# I2C_MUX.net
KiCad netlist of a schematic drawn in Altium Designer
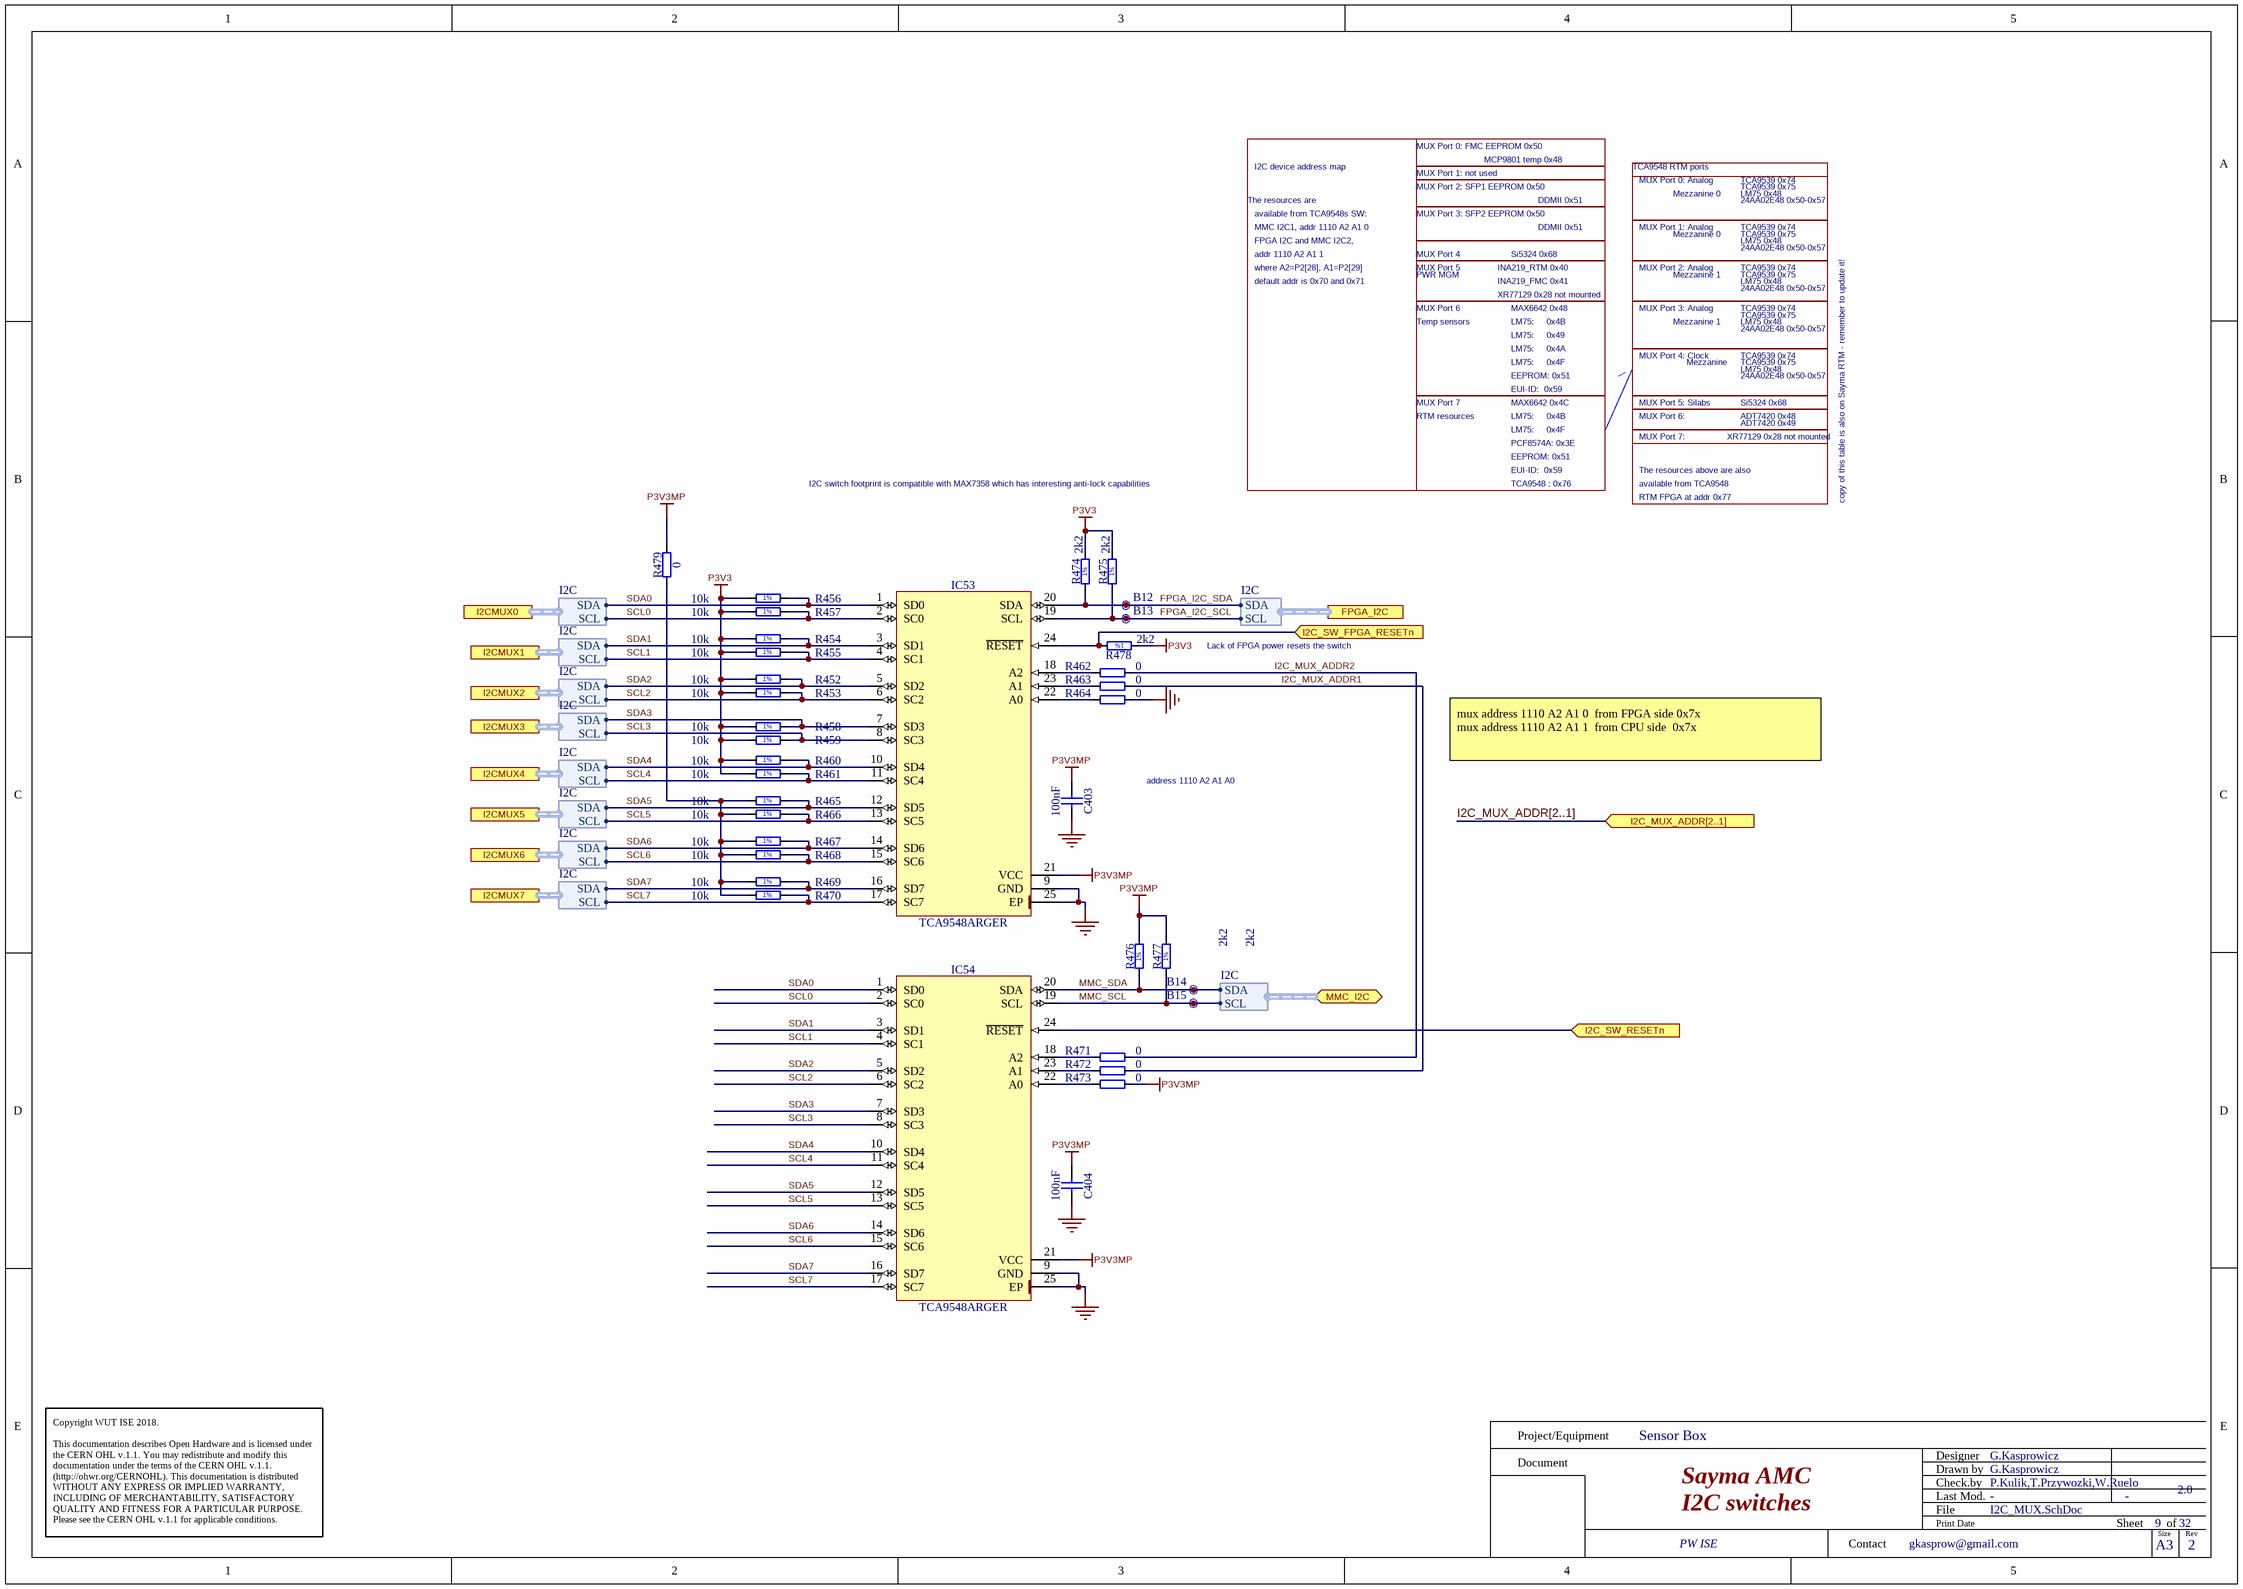
[diagram p0: I2C_MUX.SchDoc]

(export (version "E")
  (design (tool "Eeschema 10.0.6"))
  (components
    (comp (ref "B12")
      (value "SMD_PAD_D1MM")
      (footprint "C100")
      (libsource (lib "altium-import") (part "root_0__*"))
    )
    (comp (ref "B13")
      (value "SMD_PAD_D1MM")
      (footprint "C100")
      (libsource (lib "altium-import") (part "root_0__*"))
    )
    (comp (ref "B14")
      (value "SMD_PAD_D1MM")
      (footprint "C100")
      (libsource (lib "altium-import") (part "root_0__*"))
    )
    (comp (ref "B15")
      (value "SMD_PAD_D1MM")
      (footprint "C100")
      (libsource (lib "altium-import") (part "root_0__*"))
    )
    (comp (ref "C403")
      (value "100nF")
      (footprint "CAPC0603X33N")
      (description "Non-polarised capacitor")
      (fields
        (field (name "MANUFACTURER PART NUMBER") "CC0201_100NF_6.3V_10%_X5R")
        (field (name "MANUFACTURER") "GENERIC")
        (field (name "AUTHOR") "CERN DEM JLC")
      )
      (libsource (lib "Capacitors") (part "Capacitor - non polarized"))
    )
    (comp (ref "C404")
      (value "100nF")
      (footprint "CAPC0603X33N")
      (description "Non-polarised capacitor")
      (fields
        (field (name "MANUFACTURER PART NUMBER") "CC0201_100NF_6.3V_10%_X5R")
        (field (name "MANUFACTURER") "GENERIC")
        (field (name "AUTHOR") "CERN DEM JLC")
      )
      (libsource (lib "Capacitors") (part "Capacitor - non polarized"))
    )
    (comp (ref "IC53")
      (value "TCA9548ARGER")
      (footprint "QFN50P400X400X100-25N-S220")
      (description "Low Voltage 8-Channel I2C Switch With Reset")
      (fields (field (name "MANUFACTURER") "TEXAS INSTRUMENTS") (field (name "AUTHOR") "CERN DEM JLC"))
      (libsource (lib "ICs And Semiconductors") (part "TCA9548ARGER"))
    )
    (comp (ref "IC54")
      (value "TCA9548ARGER")
      (footprint "QFN50P400X400X100-25N-S220")
      (description "Low Voltage 8-Channel I2C Switch With Reset")
      (fields (field (name "MANUFACTURER") "TEXAS INSTRUMENTS") (field (name "AUTHOR") "CERN DEM JLC"))
      (libsource (lib "ICs And Semiconductors") (part "TCA9548ARGER"))
    )
    (comp (ref "R452")
      (value "10k")
      (footprint "RESC1005X40N")
      (description "Resistor - 1%")
      (fields
        (field (name "MANUFACTURER PART NUMBER") "R0402_10K_1%_0.0625W_100PPM")
        (field (name "MANUFACTURER") "GENERIC")
        (field (name "AUTHOR") "CERN DEM JLC")
      )
      (libsource (lib "Resistors") (part "Resistor - 1%"))
    )
    (comp (ref "R453")
      (value "10k")
      (footprint "RESC1005X40N")
      (description "Resistor - 1%")
      (fields
        (field (name "MANUFACTURER PART NUMBER") "R0402_10K_1%_0.0625W_100PPM")
        (field (name "MANUFACTURER") "GENERIC")
        (field (name "AUTHOR") "CERN DEM JLC")
      )
      (libsource (lib "Resistors") (part "Resistor - 1%"))
    )
    (comp (ref "R454")
      (value "10k")
      (footprint "RESC1005X40N")
      (description "Resistor - 1%")
      (fields
        (field (name "MANUFACTURER PART NUMBER") "R0402_10K_1%_0.0625W_100PPM")
        (field (name "MANUFACTURER") "GENERIC")
        (field (name "AUTHOR") "CERN DEM JLC")
      )
      (libsource (lib "Resistors") (part "Resistor - 1%"))
    )
    (comp (ref "R455")
      (value "10k")
      (footprint "RESC1005X40N")
      (description "Resistor - 1%")
      (fields
        (field (name "MANUFACTURER PART NUMBER") "R0402_10K_1%_0.0625W_100PPM")
        (field (name "MANUFACTURER") "GENERIC")
        (field (name "AUTHOR") "CERN DEM JLC")
      )
      (libsource (lib "Resistors") (part "Resistor - 1%"))
    )
    (comp (ref "R456")
      (value "10k")
      (footprint "RESC1005X40N")
      (description "Resistor - 1%")
      (fields
        (field (name "MANUFACTURER PART NUMBER") "R0402_10K_1%_0.0625W_100PPM")
        (field (name "MANUFACTURER") "GENERIC")
        (field (name "AUTHOR") "CERN DEM JLC")
      )
      (libsource (lib "Resistors") (part "Resistor - 1%"))
    )
    (comp (ref "R457")
      (value "10k")
      (footprint "RESC1005X40N")
      (description "Resistor - 1%")
      (fields
        (field (name "MANUFACTURER PART NUMBER") "R0402_10K_1%_0.0625W_100PPM")
        (field (name "MANUFACTURER") "GENERIC")
        (field (name "AUTHOR") "CERN DEM JLC")
      )
      (libsource (lib "Resistors") (part "Resistor - 1%"))
    )
    (comp (ref "R458")
      (value "10k")
      (footprint "RESC1005X40N")
      (description "Resistor - 1%")
      (fields
        (field (name "MANUFACTURER PART NUMBER") "R0402_10K_1%_0.0625W_100PPM")
        (field (name "MANUFACTURER") "GENERIC")
        (field (name "AUTHOR") "CERN DEM JLC")
      )
      (libsource (lib "Resistors") (part "Resistor - 1%"))
    )
    (comp (ref "R459")
      (value "10k")
      (footprint "RESC1005X40N")
      (description "Resistor - 1%")
      (fields
        (field (name "MANUFACTURER PART NUMBER") "R0402_10K_1%_0.0625W_100PPM")
        (field (name "MANUFACTURER") "GENERIC")
        (field (name "AUTHOR") "CERN DEM JLC")
      )
      (libsource (lib "Resistors") (part "Resistor - 1%"))
    )
    (comp (ref "R460")
      (value "10k")
      (footprint "RESC1005X40N")
      (description "Resistor - 1%")
      (fields
        (field (name "MANUFACTURER PART NUMBER") "R0402_10K_1%_0.0625W_100PPM")
        (field (name "MANUFACTURER") "GENERIC")
        (field (name "AUTHOR") "CERN DEM JLC")
      )
      (libsource (lib "Resistors") (part "Resistor - 1%"))
    )
    (comp (ref "R461")
      (value "10k")
      (footprint "RESC1005X40N")
      (description "Resistor - 1%")
      (fields
        (field (name "MANUFACTURER PART NUMBER") "R0402_10K_1%_0.0625W_100PPM")
        (field (name "MANUFACTURER") "GENERIC")
        (field (name "AUTHOR") "CERN DEM JLC")
      )
      (libsource (lib "Resistors") (part "Resistor - 1%"))
    )
    (comp (ref "R462")
      (value "0")
      (footprint "RESC1005X40N")
      (description "Resistor")
      (fields
        (field (name "MANUFACTURER PART NUMBER") "R0402_0R_JUMPER")
        (field (name "MANUFACTURER") "GENERIC")
        (field (name "AUTHOR") "CERN DEM JLC")
      )
      (libsource (lib "Resistors") (part "Resistor"))
    )
    (comp (ref "R463")
      (value "0")
      (footprint "RESC1005X40N")
      (description "Resistor")
      (fields
        (field (name "MANUFACTURER PART NUMBER") "R0402_0R_JUMPER")
        (field (name "MANUFACTURER") "GENERIC")
        (field (name "AUTHOR") "CERN DEM JLC")
      )
      (libsource (lib "Resistors") (part "Resistor"))
    )
    (comp (ref "R464")
      (value "0")
      (footprint "RESC1005X40N")
      (description "Resistor")
      (fields
        (field (name "MANUFACTURER PART NUMBER") "R0402_0R_JUMPER")
        (field (name "MANUFACTURER") "GENERIC")
        (field (name "AUTHOR") "CERN DEM JLC")
      )
      (libsource (lib "Resistors") (part "Resistor"))
    )
    (comp (ref "R465")
      (value "10k")
      (footprint "RESC1005X40N")
      (description "Resistor - 1%")
      (fields
        (field (name "MANUFACTURER PART NUMBER") "R0402_10K_1%_0.0625W_100PPM")
        (field (name "MANUFACTURER") "GENERIC")
        (field (name "AUTHOR") "CERN DEM JLC")
      )
      (libsource (lib "Resistors") (part "Resistor - 1%"))
    )
    (comp (ref "R466")
      (value "10k")
      (footprint "RESC1005X40N")
      (description "Resistor - 1%")
      (fields
        (field (name "MANUFACTURER PART NUMBER") "R0402_10K_1%_0.0625W_100PPM")
        (field (name "MANUFACTURER") "GENERIC")
        (field (name "AUTHOR") "CERN DEM JLC")
      )
      (libsource (lib "Resistors") (part "Resistor - 1%"))
    )
    (comp (ref "R467")
      (value "10k")
      (footprint "RESC1005X40N")
      (description "Resistor - 1%")
      (fields
        (field (name "MANUFACTURER PART NUMBER") "R0402_10K_1%_0.0625W_100PPM")
        (field (name "MANUFACTURER") "GENERIC")
        (field (name "AUTHOR") "CERN DEM JLC")
      )
      (libsource (lib "Resistors") (part "Resistor - 1%"))
    )
    (comp (ref "R468")
      (value "10k")
      (footprint "RESC1005X40N")
      (description "Resistor - 1%")
      (fields
        (field (name "MANUFACTURER PART NUMBER") "R0402_10K_1%_0.0625W_100PPM")
        (field (name "MANUFACTURER") "GENERIC")
        (field (name "AUTHOR") "CERN DEM JLC")
      )
      (libsource (lib "Resistors") (part "Resistor - 1%"))
    )
    (comp (ref "R469")
      (value "10k")
      (footprint "RESC1005X40N")
      (description "Resistor - 1%")
      (fields
        (field (name "MANUFACTURER PART NUMBER") "R0402_10K_1%_0.0625W_100PPM")
        (field (name "MANUFACTURER") "GENERIC")
        (field (name "AUTHOR") "CERN DEM JLC")
      )
      (libsource (lib "Resistors") (part "Resistor - 1%"))
    )
    (comp (ref "R470")
      (value "10k")
      (footprint "RESC1005X40N")
      (description "Resistor - 1%")
      (fields
        (field (name "MANUFACTURER PART NUMBER") "R0402_10K_1%_0.0625W_100PPM")
        (field (name "MANUFACTURER") "GENERIC")
        (field (name "AUTHOR") "CERN DEM JLC")
      )
      (libsource (lib "Resistors") (part "Resistor - 1%"))
    )
    (comp (ref "R471")
      (value "0")
      (footprint "RESC1005X40N")
      (description "Resistor")
      (fields
        (field (name "MANUFACTURER PART NUMBER") "R0402_0R_JUMPER")
        (field (name "MANUFACTURER") "GENERIC")
        (field (name "AUTHOR") "CERN DEM JLC")
      )
      (libsource (lib "Resistors") (part "Resistor"))
    )
    (comp (ref "R472")
      (value "0")
      (footprint "RESC1005X40N")
      (description "Resistor")
      (fields
        (field (name "MANUFACTURER PART NUMBER") "R0402_0R_JUMPER")
        (field (name "MANUFACTURER") "GENERIC")
        (field (name "AUTHOR") "CERN DEM JLC")
      )
      (libsource (lib "Resistors") (part "Resistor"))
    )
    (comp (ref "R473")
      (value "0")
      (footprint "RESC1005X40N")
      (description "Resistor")
      (fields
        (field (name "MANUFACTURER PART NUMBER") "R0402_0R_JUMPER")
        (field (name "MANUFACTURER") "GENERIC")
        (field (name "AUTHOR") "CERN DEM JLC")
      )
      (libsource (lib "Resistors") (part "Resistor"))
    )
    (comp (ref "R474")
      (value "2k2")
      (footprint "RESC1005X40N")
      (description "Resistor - 1%")
      (fields
        (field (name "MANUFACTURER PART NUMBER") "R0402_2K2_1%_0.0625W_100PPM")
        (field (name "MANUFACTURER") "GENERIC")
        (field (name "AUTHOR") "CERN DEM JLC")
      )
      (libsource (lib "Resistors") (part "Resistor - 1%"))
    )
    (comp (ref "R475")
      (value "2k2")
      (footprint "RESC1005X40N")
      (description "Resistor - 1%")
      (fields
        (field (name "MANUFACTURER PART NUMBER") "R0402_2K2_1%_0.0625W_100PPM")
        (field (name "MANUFACTURER") "GENERIC")
        (field (name "AUTHOR") "CERN DEM JLC")
      )
      (libsource (lib "Resistors") (part "Resistor - 1%"))
    )
    (comp (ref "R476")
      (value "2k2")
      (footprint "RESC1005X40N")
      (description "Resistor - 1%")
      (fields
        (field (name "MANUFACTURER PART NUMBER") "R0402_2K2_1%_0.0625W_100PPM")
        (field (name "MANUFACTURER") "GENERIC")
        (field (name "AUTHOR") "CERN DEM JLC")
      )
      (libsource (lib "Resistors") (part "Resistor - 1%"))
    )
    (comp (ref "R477")
      (value "2k2")
      (footprint "RESC1005X40N")
      (description "Resistor - 1%")
      (fields
        (field (name "MANUFACTURER PART NUMBER") "R0402_2K2_1%_0.0625W_100PPM")
        (field (name "MANUFACTURER") "GENERIC")
        (field (name "AUTHOR") "CERN DEM JLC")
      )
      (libsource (lib "Resistors") (part "Resistor - 1%"))
    )
    (comp (ref "R478")
      (value "2k2")
      (footprint "RESC1005X40N")
      (description "Resistor - 1%")
      (fields
        (field (name "MANUFACTURER PART NUMBER") "R0402_2K2_1%_0.0625W_100PPM")
        (field (name "MANUFACTURER") "GENERIC")
        (field (name "AUTHOR") "CERN DEM JLC")
      )
      (libsource (lib "Resistors") (part "Resistor - 1%"))
    )
    (comp (ref "R479")
      (value "0")
      (footprint "RESC1005X40N")
      (description "Resistor")
      (fields
        (field (name "MANUFACTURER PART NUMBER") "R0402_0R_JUMPER")
        (field (name "MANUFACTURER") "GENERIC")
        (field (name "AUTHOR") "CERN DEM JLC")
      )
      (libsource (lib "Resistors") (part "Resistor"))
    )
  )
  (nets
    (net (code "2") (name "/FPGA_I2C_SCL") (class "Default")
      (node (ref "B13") (pin "1") (pinfunction "1_1") (pintype "passive"))
      (node (ref "IC53") (pin "19") (pinfunction "SCL_19") (pintype "bidirectional"))
      (node (ref "R475") (pin "1") (pinfunction "1_1") (pintype "passive"))
    )
    (net (code "3") (name "/FPGA_I2C_SDA") (class "Default")
      (node (ref "B12") (pin "1") (pinfunction "1_1") (pintype "passive"))
      (node (ref "IC53") (pin "20") (pinfunction "SDA_20") (pintype "bidirectional"))
      (node (ref "R474") (pin "1") (pinfunction "1_1") (pintype "passive"))
    )
    (net (code "4") (name "/I2C_MUX_ADDR1") (class "Default")
      (node (ref "R463") (pin "1") (pinfunction "1_1") (pintype "passive"))
      (node (ref "R472") (pin "1") (pinfunction "1_1") (pintype "passive"))
    )
    (net (code "5") (name "/I2C_MUX_ADDR2") (class "Default")
      (node (ref "R462") (pin "1") (pinfunction "1_1") (pintype "passive"))
      (node (ref "R471") (pin "1") (pinfunction "1_1") (pintype "passive"))
    )
    (net (code "7") (name "/I2C_SW_FPGA_RESETn") (class "Default")
      (node (ref "IC53") (pin "24") (pinfunction "~{RESET}_24") (pintype "input"))
      (node (ref "R478") (pin "2") (pinfunction "2_2") (pintype "passive"))
    )
    (net (code "8") (name "/I2C_SW_RESETn") (class "Default")
      (node (ref "IC54") (pin "24") (pinfunction "~{RESET}_24") (pintype "input"))
    )
    (net (code "9") (name "/MMC_SCL") (class "Default")
      (node (ref "B15") (pin "1") (pinfunction "1_1") (pintype "passive"))
      (node (ref "IC54") (pin "19") (pinfunction "SCL_19") (pintype "bidirectional"))
      (node (ref "R477") (pin "1") (pinfunction "1_1") (pintype "passive"))
    )
    (net (code "10") (name "/MMC_SDA") (class "Default")
      (node (ref "B14") (pin "1") (pinfunction "1_1") (pintype "passive"))
      (node (ref "IC54") (pin "20") (pinfunction "SDA_20") (pintype "bidirectional"))
      (node (ref "R476") (pin "1") (pinfunction "1_1") (pintype "passive"))
    )
    (net (code "11") (name "/SCL0") (class "Default")
      (node (ref "IC53") (pin "2") (pinfunction "SC0_2") (pintype "bidirectional"))
      (node (ref "IC54") (pin "2") (pinfunction "SC0_2") (pintype "bidirectional"))
      (node (ref "R457") (pin "2") (pinfunction "2_2") (pintype "passive"))
    )
    (net (code "12") (name "/SCL1") (class "Default")
      (node (ref "IC53") (pin "4") (pinfunction "SC1_4") (pintype "bidirectional"))
      (node (ref "IC54") (pin "4") (pinfunction "SC1_4") (pintype "bidirectional"))
      (node (ref "R455") (pin "2") (pinfunction "2_2") (pintype "passive"))
    )
    (net (code "13") (name "/SCL2") (class "Default")
      (node (ref "IC53") (pin "6") (pinfunction "SC2_6") (pintype "bidirectional"))
      (node (ref "IC54") (pin "6") (pinfunction "SC2_6") (pintype "bidirectional"))
      (node (ref "R453") (pin "2") (pinfunction "2_2") (pintype "passive"))
    )
    (net (code "14") (name "/SCL3") (class "Default")
      (node (ref "IC53") (pin "8") (pinfunction "SC3_8") (pintype "bidirectional"))
      (node (ref "IC54") (pin "8") (pinfunction "SC3_8") (pintype "bidirectional"))
      (node (ref "R459") (pin "2") (pinfunction "2_2") (pintype "passive"))
    )
    (net (code "15") (name "/SCL4") (class "Default")
      (node (ref "IC53") (pin "11") (pinfunction "SC4_11") (pintype "bidirectional"))
      (node (ref "IC54") (pin "11") (pinfunction "SC4_11") (pintype "bidirectional"))
      (node (ref "R461") (pin "2") (pinfunction "2_2") (pintype "passive"))
    )
    (net (code "16") (name "/SCL5") (class "Default")
      (node (ref "IC53") (pin "13") (pinfunction "SC5_13") (pintype "bidirectional"))
      (node (ref "IC54") (pin "13") (pinfunction "SC5_13") (pintype "bidirectional"))
      (node (ref "R466") (pin "2") (pinfunction "2_2") (pintype "passive"))
    )
    (net (code "17") (name "/SCL6") (class "Default")
      (node (ref "IC53") (pin "15") (pinfunction "SC6_15") (pintype "bidirectional"))
      (node (ref "IC54") (pin "15") (pinfunction "SC6_15") (pintype "bidirectional"))
      (node (ref "R468") (pin "2") (pinfunction "2_2") (pintype "passive"))
    )
    (net (code "18") (name "/SCL7") (class "Default")
      (node (ref "IC53") (pin "17") (pinfunction "SC7_17") (pintype "bidirectional"))
      (node (ref "IC54") (pin "17") (pinfunction "SC7_17") (pintype "bidirectional"))
      (node (ref "R470") (pin "2") (pinfunction "2_2") (pintype "passive"))
    )
    (net (code "19") (name "/SDA0") (class "Default")
      (node (ref "IC53") (pin "1") (pinfunction "SD0_1") (pintype "bidirectional"))
      (node (ref "IC54") (pin "1") (pinfunction "SD0_1") (pintype "bidirectional"))
      (node (ref "R456") (pin "2") (pinfunction "2_2") (pintype "passive"))
    )
    (net (code "20") (name "/SDA1") (class "Default")
      (node (ref "IC53") (pin "3") (pinfunction "SD1_3") (pintype "bidirectional"))
      (node (ref "IC54") (pin "3") (pinfunction "SD1_3") (pintype "bidirectional"))
      (node (ref "R454") (pin "2") (pinfunction "2_2") (pintype "passive"))
    )
    (net (code "21") (name "/SDA2") (class "Default")
      (node (ref "IC53") (pin "5") (pinfunction "SD2_5") (pintype "bidirectional"))
      (node (ref "IC54") (pin "5") (pinfunction "SD2_5") (pintype "bidirectional"))
      (node (ref "R452") (pin "2") (pinfunction "2_2") (pintype "passive"))
    )
    (net (code "22") (name "/SDA3") (class "Default")
      (node (ref "IC53") (pin "7") (pinfunction "SD3_7") (pintype "bidirectional"))
      (node (ref "IC54") (pin "7") (pinfunction "SD3_7") (pintype "bidirectional"))
      (node (ref "R458") (pin "2") (pinfunction "2_2") (pintype "passive"))
    )
    (net (code "23") (name "/SDA4") (class "Default")
      (node (ref "IC53") (pin "10") (pinfunction "SD4_10") (pintype "bidirectional"))
      (node (ref "IC54") (pin "10") (pinfunction "SD4_10") (pintype "bidirectional"))
      (node (ref "R460") (pin "2") (pinfunction "2_2") (pintype "passive"))
    )
    (net (code "24") (name "/SDA5") (class "Default")
      (node (ref "IC53") (pin "12") (pinfunction "SD5_12") (pintype "bidirectional"))
      (node (ref "IC54") (pin "12") (pinfunction "SD5_12") (pintype "bidirectional"))
      (node (ref "R465") (pin "2") (pinfunction "2_2") (pintype "passive"))
    )
    (net (code "25") (name "/SDA6") (class "Default")
      (node (ref "IC53") (pin "14") (pinfunction "SD6_14") (pintype "bidirectional"))
      (node (ref "IC54") (pin "14") (pinfunction "SD6_14") (pintype "bidirectional"))
      (node (ref "R467") (pin "2") (pinfunction "2_2") (pintype "passive"))
    )
    (net (code "26") (name "/SDA7") (class "Default")
      (node (ref "IC53") (pin "16") (pinfunction "SD7_16") (pintype "bidirectional"))
      (node (ref "IC54") (pin "16") (pinfunction "SD7_16") (pintype "bidirectional"))
      (node (ref "R469") (pin "2") (pinfunction "2_2") (pintype "passive"))
    )
    (net (code "28") (name "GND") (class "Default")
      (node (ref "C403") (pin "2") (pinfunction "2_2") (pintype "passive"))
      (node (ref "C404") (pin "2") (pinfunction "2_2") (pintype "passive"))
      (node (ref "IC53") (pin "25") (pinfunction "EP_25") (pintype "power_in"))
      (node (ref "IC53") (pin "9") (pinfunction "GND_9") (pintype "power_in"))
      (node (ref "IC54") (pin "25") (pinfunction "EP_25") (pintype "power_in"))
      (node (ref "IC54") (pin "9") (pinfunction "GND_9") (pintype "power_in"))
      (node (ref "R464") (pin "1") (pinfunction "1_1") (pintype "passive"))
    )
    (net (code "29") (name "Net-(IC53-A0)") (class "Default")
      (node (ref "IC53") (pin "22") (pinfunction "A0_22") (pintype "input"))
      (node (ref "R464") (pin "2") (pinfunction "2_2") (pintype "passive"))
    )
    (net (code "30") (name "Net-(IC53-A1)") (class "Default")
      (node (ref "IC53") (pin "23") (pinfunction "A1_23") (pintype "input"))
      (node (ref "R463") (pin "2") (pinfunction "2_2") (pintype "passive"))
    )
    (net (code "31") (name "Net-(IC53-A2)") (class "Default")
      (node (ref "IC53") (pin "18") (pinfunction "A2_18") (pintype "input"))
      (node (ref "R462") (pin "2") (pinfunction "2_2") (pintype "passive"))
    )
    (net (code "32") (name "Net-(IC54-A0)") (class "Default")
      (node (ref "IC54") (pin "22") (pinfunction "A0_22") (pintype "input"))
      (node (ref "R473") (pin "2") (pinfunction "2_2") (pintype "passive"))
    )
    (net (code "33") (name "Net-(IC54-A1)") (class "Default")
      (node (ref "IC54") (pin "23") (pinfunction "A1_23") (pintype "input"))
      (node (ref "R472") (pin "2") (pinfunction "2_2") (pintype "passive"))
    )
    (net (code "34") (name "Net-(IC54-A2)") (class "Default")
      (node (ref "IC54") (pin "18") (pinfunction "A2_18") (pintype "input"))
      (node (ref "R471") (pin "2") (pinfunction "2_2") (pintype "passive"))
    )
    (net (code "35") (name "Net-(R465-Pad1)") (class "Default")
      (node (ref "R465") (pin "1") (pinfunction "1_1") (pintype "passive"))
      (node (ref "R466") (pin "1") (pinfunction "1_1") (pintype "passive"))
      (node (ref "R467") (pin "1") (pinfunction "1_1") (pintype "passive"))
      (node (ref "R468") (pin "1") (pinfunction "1_1") (pintype "passive"))
      (node (ref "R469") (pin "1") (pinfunction "1_1") (pintype "passive"))
      (node (ref "R470") (pin "1") (pinfunction "1_1") (pintype "passive"))
      (node (ref "R479") (pin "2") (pinfunction "2_2") (pintype "passive"))
    )
    (net (code "36") (name "P3V3") (class "Default")
      (node (ref "R452") (pin "1") (pinfunction "1_1") (pintype "passive"))
      (node (ref "R453") (pin "1") (pinfunction "1_1") (pintype "passive"))
      (node (ref "R454") (pin "1") (pinfunction "1_1") (pintype "passive"))
      (node (ref "R455") (pin "1") (pinfunction "1_1") (pintype "passive"))
      (node (ref "R456") (pin "1") (pinfunction "1_1") (pintype "passive"))
      (node (ref "R457") (pin "1") (pinfunction "1_1") (pintype "passive"))
      (node (ref "R458") (pin "1") (pinfunction "1_1") (pintype "passive"))
      (node (ref "R459") (pin "1") (pinfunction "1_1") (pintype "passive"))
      (node (ref "R460") (pin "1") (pinfunction "1_1") (pintype "passive"))
      (node (ref "R461") (pin "1") (pinfunction "1_1") (pintype "passive"))
      (node (ref "R474") (pin "2") (pinfunction "2_2") (pintype "passive"))
      (node (ref "R475") (pin "2") (pinfunction "2_2") (pintype "passive"))
      (node (ref "R478") (pin "1") (pinfunction "1_1") (pintype "passive"))
    )
    (net (code "37") (name "P3V3MP") (class "Default")
      (node (ref "C403") (pin "1") (pinfunction "1_1") (pintype "passive"))
      (node (ref "C404") (pin "1") (pinfunction "1_1") (pintype "passive"))
      (node (ref "IC53") (pin "21") (pinfunction "VCC_21") (pintype "power_in"))
      (node (ref "IC54") (pin "21") (pinfunction "VCC_21") (pintype "power_in"))
      (node (ref "R473") (pin "1") (pinfunction "1_1") (pintype "passive"))
      (node (ref "R476") (pin "2") (pinfunction "2_2") (pintype "passive"))
      (node (ref "R477") (pin "2") (pinfunction "2_2") (pintype "passive"))
      (node (ref "R479") (pin "1") (pinfunction "1_1") (pintype "passive"))
    )
  )
)
